# power.net
KiCad netlist of a schematic drawn in Altium Designer
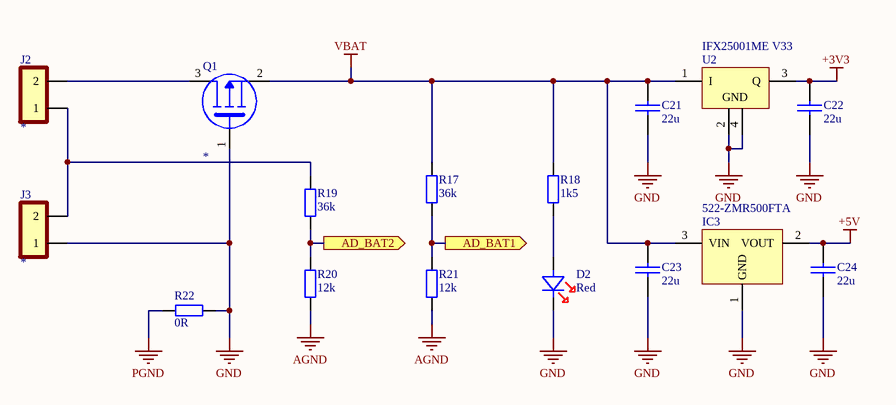
[diagram p0: power.SchDoc]

(export (version "E")
  (design (tool "Eeschema 10.0.6"))
  (components
    (comp (ref "C21")
      (value "22u")
      (footprint "C0603_PASTE")
      (description "Multilayer Ceramic Capacitors MLCC - SMD 0603")
      (libsource (lib "Passives") (part "C-0603"))
    )
    (comp (ref "C22")
      (value "22u")
      (footprint "C0603_PASTE")
      (description "Multilayer Ceramic Capacitors MLCC - SMD 0603")
      (libsource (lib "Passives") (part "C-0603"))
    )
    (comp (ref "C23")
      (value "22u")
      (footprint "C0603_PASTE")
      (description "Multilayer Ceramic Capacitors MLCC - SMD 0603")
      (libsource (lib "Passives") (part "C-0603"))
    )
    (comp (ref "C24")
      (value "22u")
      (footprint "C0603_PASTE")
      (description "Multilayer Ceramic Capacitors MLCC - SMD 0603")
      (libsource (lib "Passives") (part "C-0603"))
    )
    (comp (ref "D2")
      (value "Red")
      (footprint "LED0402_RED")
      (description "Standard LEDs - SMD SMD 0402 Red")
      (fields (field (name "MANUFACTURER") "SunLED"))
      (libsource (lib "Discrete") (part "LED_0402_Red"))
    )
    (comp (ref "IC3")
      (value "ZMR500FTA")
      (footprint "SOT-23")
      (description "IC REG LINEAR 5V 50MA SOT23-3")
      (fields (field (name "SUPPLIER PART NUMBER 1") "522-ZMR500FTA"))
      (libsource (lib "ICs") (part "ZMR500FTA"))
    )
    (comp (ref "J2")
      (value "*")
      (footprint "CON-2x1-JMP")
      (description "2 Positions Header 2.54mm")
      (fields (field (name "MANUFACTURER") "Molex, LLC"))
      (libsource (lib "Connectors") (part "CON-2x1-JMP"))
    )
    (comp (ref "J3")
      (value "*")
      (footprint "CON-2x1-JMP")
      (description "2 Positions Header 2.54mm")
      (fields (field (name "MANUFACTURER") "Molex, LLC"))
      (libsource (lib "Connectors") (part "CON-2x1-JMP"))
    )
    (comp (ref "Q1")
      (value "*")
      (footprint "SOT-23")
      (description "MOSFET P-CH  SOT23")
      (fields (field (name "MANUFACTURER") "Diodes Incorporated"))
      (libsource (lib "Discrete") (part "MOSFET-P"))
    )
    (comp (ref "R17")
      (value "36k")
      (footprint "R0603_PASTE")
      (description "RES SMD 0603")
      (libsource (lib "Passives") (part "R-0603"))
    )
    (comp (ref "R18")
      (value "1k5")
      (footprint "R0603_PASTE")
      (description "RES SMD 0603")
      (libsource (lib "Passives") (part "R-0603"))
    )
    (comp (ref "R19")
      (value "36k")
      (footprint "R0603_PASTE")
      (description "RES SMD 0603")
      (libsource (lib "Passives") (part "R-0603"))
    )
    (comp (ref "R20")
      (value "12k")
      (footprint "R0603_PASTE")
      (description "RES SMD 0603")
      (libsource (lib "Passives") (part "R-0603"))
    )
    (comp (ref "R21")
      (value "12k")
      (footprint "R0603_PASTE")
      (description "RES SMD 0603")
      (libsource (lib "Passives") (part "R-0603"))
    )
    (comp (ref "R22")
      (value "0R")
      (footprint "R0201-paste")
      (description "RES SMD 0201")
      (libsource (lib "Passives") (part "R-0201"))
    )
    (comp (ref "U2")
      (value "IFX25001ME V33")
      (footprint "INF-PG-SOT223_SC-73_L")
      (fields (field (name "MANUFACTURER") "Infineon"))
      (libsource (lib "Altium Content Vault") (part "INF-IFX25001MEV33-PG-SOT223-4"))
    )
  )
  (nets
    (net (code "1") (name "+3V3") (class "Default")
      (node (ref "C22") (pin "1") (pintype "passive"))
      (node (ref "U2") (pin "3") (pinfunction "Q_3") (pintype "power_in"))
    )
    (net (code "2") (name "+5V") (class "Default")
      (node (ref "C24") (pin "1") (pintype "passive"))
      (node (ref "IC3") (pin "2") (pinfunction "VOUT_2") (pintype "power_in"))
    )
    (net (code "3") (name "/AD_BAT1") (class "Default")
      (node (ref "R17") (pin "2") (pinfunction "2_2") (pintype "passive"))
      (node (ref "R21") (pin "1") (pinfunction "1_1") (pintype "passive"))
    )
    (net (code "4") (name "/AD_BAT2") (class "Default")
      (node (ref "R19") (pin "2") (pinfunction "2_2") (pintype "passive"))
      (node (ref "R20") (pin "1") (pinfunction "1_1") (pintype "passive"))
    )
    (net (code "5") (name "AGND") (class "Default")
      (node (ref "R20") (pin "2") (pinfunction "2_2") (pintype "passive"))
      (node (ref "R21") (pin "2") (pinfunction "2_2") (pintype "passive"))
    )
    (net (code "6") (name "GND") (class "Default")
      (node (ref "C21") (pin "2") (pintype "passive"))
      (node (ref "C22") (pin "2") (pintype "passive"))
      (node (ref "C23") (pin "2") (pintype "passive"))
      (node (ref "C24") (pin "2") (pintype "passive"))
      (node (ref "D2") (pin "2") (pinfunction "CATHODE_2") (pintype "passive"))
      (node (ref "IC3") (pin "1") (pinfunction "GND_1") (pintype "power_in"))
      (node (ref "J3") (pin "1") (pinfunction "1_1") (pintype "passive"))
      (node (ref "Q1") (pin "1") (pinfunction "GATE_1") (pintype "passive"))
      (node (ref "R22") (pin "2") (pinfunction "2_2") (pintype "passive"))
      (node (ref "U2") (pin "2") (pinfunction "GND_2") (pintype "power_in"))
      (node (ref "U2") (pin "4") (pinfunction "GND_4") (pintype "power_in"))
    )
    (net (code "7") (name "Net-(D2-ANODE)") (class "Default")
      (node (ref "D2") (pin "1") (pinfunction "ANODE_1") (pintype "passive"))
      (node (ref "R18") (pin "2") (pinfunction "2_2") (pintype "passive"))
    )
    (net (code "8") (name "Net-(J2-Pad1)") (class "Default")
      (node (ref "J2") (pin "1") (pinfunction "1_1") (pintype "passive"))
      (node (ref "J3") (pin "2") (pinfunction "2_2") (pintype "passive"))
      (node (ref "R19") (pin "1") (pinfunction "1_1") (pintype "passive"))
    )
    (net (code "9") (name "Net-(Q1-SOURCE)") (class "Default")
      (node (ref "J2") (pin "2") (pinfunction "2_2") (pintype "passive"))
      (node (ref "Q1") (pin "3") (pinfunction "SOURCE_3") (pintype "passive"))
    )
    (net (code "10") (name "PGND") (class "Default")
      (node (ref "R22") (pin "1") (pinfunction "1_1") (pintype "passive"))
    )
    (net (code "11") (name "VBAT") (class "Default")
      (node (ref "C21") (pin "1") (pintype "passive"))
      (node (ref "C23") (pin "1") (pintype "passive"))
      (node (ref "IC3") (pin "3") (pinfunction "VIN_3") (pintype "power_in"))
      (node (ref "Q1") (pin "2") (pinfunction "DRAIN_2") (pintype "passive"))
      (node (ref "R17") (pin "1") (pinfunction "1_1") (pintype "passive"))
      (node (ref "R18") (pin "1") (pinfunction "1_1") (pintype "passive"))
      (node (ref "U2") (pin "1") (pinfunction "I_1") (pintype "power_in"))
    )
  )
)
